# SCHEMATIC_board.net
KiCad netlist of a schematic drawn in EAGLE
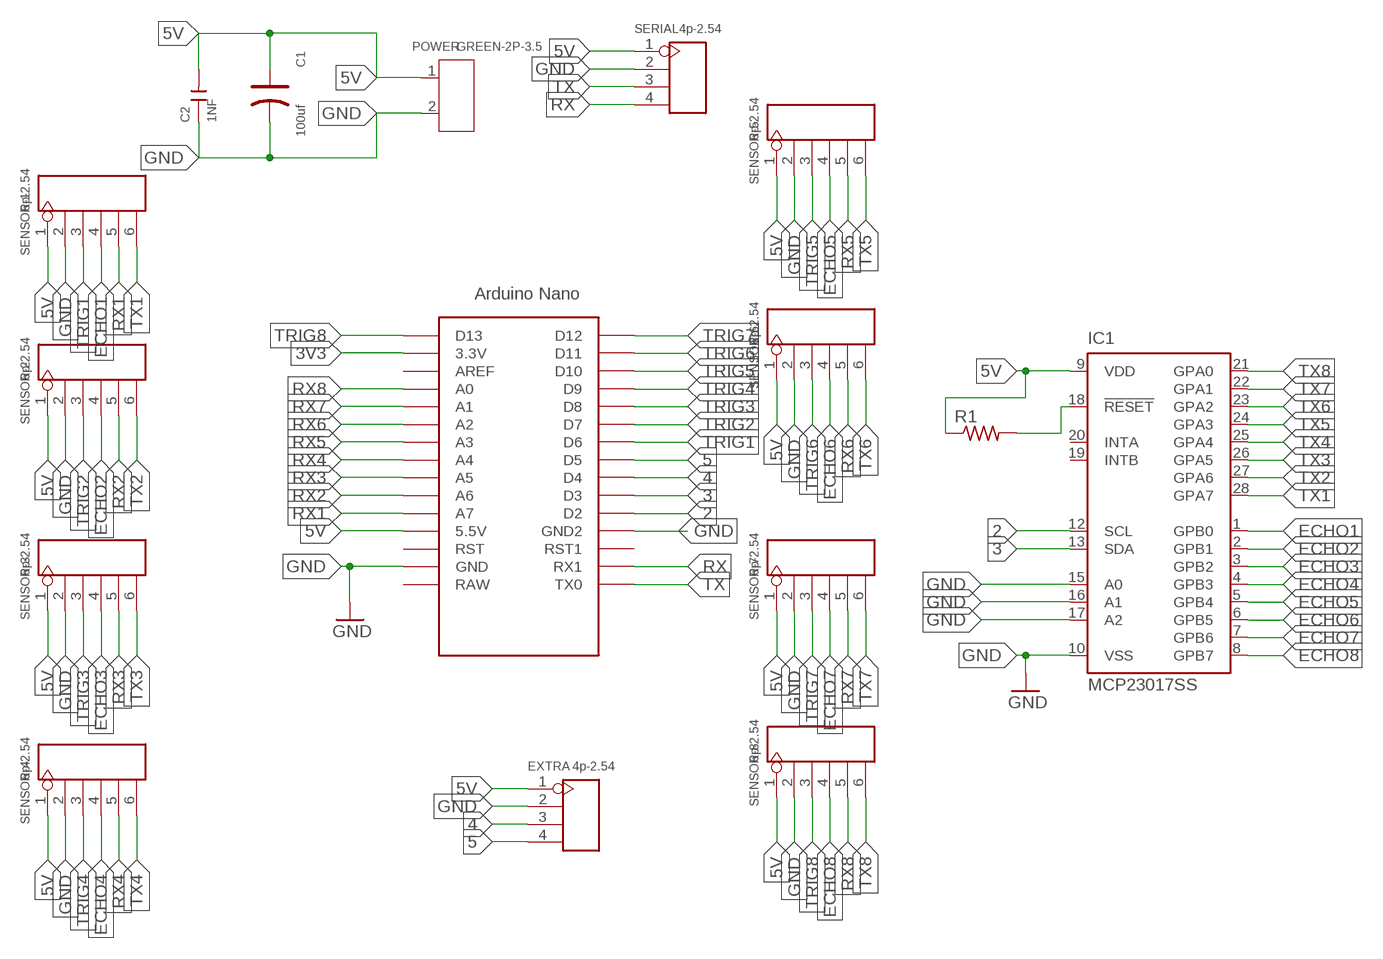
[diagram p0: schematic, sheet 1]

(export (version "E")
  (design (tool "Eeschema 10.0.6"))
  (components
    (comp (ref "C1")
      (value "100uf")
      (footprint "eagle-import:PC-D5.3MM")
      (fields (field (name "MPN") "KS 100uF/16V"))
      (libsource (lib "eagle-import") (part "DIP-ALUMINUM-100UF-16V(D5-H7MM)"))
    )
    (comp (ref "C2")
      (value "1NF")
      (footprint "eagle-import:C1206")
      (fields (field (name "MPN") "CC1206KKX7RCBB102"))
      (libsource (lib "eagle-import") (part "CERAMIC-1NF-1KV-10%-X7R?(1206)"))
    )
    (comp (ref "EXTRA")
      (value "4p-2.54")
      (footprint "eagle-import:H4-2.54")
      (fields (field (name "MPN") "P125-1104A0BS116A1"))
      (libsource (lib "eagle-import") (part "DIP-BLACK-MALE-HEADER-VERT(4P-2.54)"))
    )
    (comp (ref "IC1")
      (value "MCP23017SS")
      (footprint "eagle-import:SSOP28")
      (libsource (lib "eagle-import") (part "MCP23017SS"))
    )
    (comp (ref "POWER")
      (value "GREEN-2P-3.5")
      (footprint "eagle-import:H2-3.5-7.0X7.0MM")
      (libsource (lib "eagle-import") (part "SCREW-TERMINAL-GREEN(2P-3.5)"))
    )
    (comp (ref "R1")
      (value "R-US_M1206")
      (footprint "eagle-import:M1206")
      (libsource (lib "eagle-import") (part "R-US_M1206"))
    )
    (comp (ref "SENSOR-1")
      (value "6p-2.54")
      (footprint "eagle-import:H6-2.54")
      (fields (field (name "MPN") "F185-1106A1BSYC1"))
      (libsource (lib "eagle-import") (part "DIP-BLACK-FEMALE-HEADER-VERT(6P-2.54)"))
    )
    (comp (ref "SENSOR-2")
      (value "6p-2.54")
      (footprint "eagle-import:H6-2.54")
      (fields (field (name "MPN") "F185-1106A1BSYC1"))
      (libsource (lib "eagle-import") (part "DIP-BLACK-FEMALE-HEADER-VERT(6P-2.54)"))
    )
    (comp (ref "SENSOR-3")
      (value "6p-2.54")
      (footprint "eagle-import:H6-2.54")
      (fields (field (name "MPN") "F185-1106A1BSYC1"))
      (libsource (lib "eagle-import") (part "DIP-BLACK-FEMALE-HEADER-VERT(6P-2.54)"))
    )
    (comp (ref "SENSOR-4")
      (value "6p-2.54")
      (footprint "eagle-import:H6-2.54")
      (fields (field (name "MPN") "F185-1106A1BSYC1"))
      (libsource (lib "eagle-import") (part "DIP-BLACK-FEMALE-HEADER-VERT(6P-2.54)"))
    )
    (comp (ref "SENSOR-5")
      (value "6p-2.54")
      (footprint "eagle-import:H6-2.54")
      (fields (field (name "MPN") "F185-1106A1BSYC1"))
      (libsource (lib "eagle-import") (part "DIP-BLACK-FEMALE-HEADER-VERT(6P-2.54)"))
    )
    (comp (ref "SENSOR-6")
      (value "6p-2.54")
      (footprint "eagle-import:H6-2.54")
      (fields (field (name "MPN") "F185-1106A1BSYC1"))
      (libsource (lib "eagle-import") (part "DIP-BLACK-FEMALE-HEADER-VERT(6P-2.54)"))
    )
    (comp (ref "SENSOR-7")
      (value "6p-2.54")
      (footprint "eagle-import:H6-2.54")
      (fields (field (name "MPN") "F185-1106A1BSYC1"))
      (libsource (lib "eagle-import") (part "DIP-BLACK-FEMALE-HEADER-VERT(6P-2.54)"))
    )
    (comp (ref "SENSOR-8")
      (value "6p-2.54")
      (footprint "eagle-import:H6-2.54")
      (fields (field (name "MPN") "F185-1106A1BSYC1"))
      (libsource (lib "eagle-import") (part "DIP-BLACK-FEMALE-HEADER-VERT(6P-2.54)"))
    )
    (comp (ref "SERIAL")
      (value "4p-2.54")
      (footprint "eagle-import:H4-2.54")
      (fields (field (name "MPN") "P125-1104A0BS116A1"))
      (libsource (lib "eagle-import") (part "DIP-BLACK-MALE-HEADER-VERT(4P-2.54)"))
    )
    (comp (ref "U$1")
      (value "NANO")
      (footprint "eagle-import:NANO")
      (libsource (lib "eagle-import") (part "NANO"))
    )
  )
  (nets
    (net (code "1") (name "2") (class "Default")
      (node (ref "IC1") (pin "12") (pinfunction "SCL_12") (pintype "input"))
      (node (ref "U$1") (pin "D2") (pinfunction "D2_D2") (pintype "bidirectional"))
    )
    (net (code "2") (name "3") (class "Default")
      (node (ref "IC1") (pin "13") (pinfunction "SDA_13") (pintype "bidirectional"))
      (node (ref "U$1") (pin "D3") (pinfunction "D3_D3") (pintype "bidirectional"))
    )
    (net (code "3") (name "3V3") (class "Default")
      (node (ref "U$1") (pin "3.3V") (pinfunction "3.3V_3.3V") (pintype "bidirectional"))
    )
    (net (code "4") (name "4") (class "Default")
      (node (ref "EXTRA") (pin "3") (pinfunction "P$3_3") (pintype "bidirectional"))
      (node (ref "U$1") (pin "D4") (pinfunction "D4_D4") (pintype "bidirectional"))
    )
    (net (code "5") (name "5") (class "Default")
      (node (ref "EXTRA") (pin "4") (pinfunction "P$4_4") (pintype "bidirectional"))
      (node (ref "U$1") (pin "D5") (pinfunction "D5_D5") (pintype "bidirectional"))
    )
    (net (code "6") (name "5V") (class "Default")
      (node (ref "C1") (pin "+") (pinfunction "+_+") (pintype "passive"))
      (node (ref "C2") (pin "2") (pinfunction "2_2") (pintype "passive"))
      (node (ref "EXTRA") (pin "1") (pinfunction "P$1_1") (pintype "bidirectional"))
      (node (ref "IC1") (pin "9") (pinfunction "VDD_9") (pintype "power_in"))
      (node (ref "POWER") (pin "1") (pinfunction "1_1") (pintype "bidirectional"))
      (node (ref "R1") (pin "1") (pinfunction "1_1") (pintype "passive"))
      (node (ref "SENSOR-1") (pin "1") (pinfunction "1_1") (pintype "bidirectional"))
      (node (ref "SENSOR-2") (pin "1") (pinfunction "1_1") (pintype "bidirectional"))
      (node (ref "SENSOR-3") (pin "1") (pinfunction "1_1") (pintype "bidirectional"))
      (node (ref "SENSOR-4") (pin "1") (pinfunction "1_1") (pintype "bidirectional"))
      (node (ref "SENSOR-5") (pin "1") (pinfunction "1_1") (pintype "bidirectional"))
      (node (ref "SENSOR-6") (pin "1") (pinfunction "1_1") (pintype "bidirectional"))
      (node (ref "SENSOR-7") (pin "1") (pinfunction "1_1") (pintype "bidirectional"))
      (node (ref "SENSOR-8") (pin "1") (pinfunction "1_1") (pintype "bidirectional"))
      (node (ref "SERIAL") (pin "1") (pinfunction "P$1_1") (pintype "bidirectional"))
      (node (ref "U$1") (pin "5V") (pinfunction "5.5V_5V") (pintype "bidirectional"))
    )
    (net (code "7") (name "ECHO1") (class "Default")
      (node (ref "IC1") (pin "1") (pinfunction "GPB0_1") (pintype "bidirectional"))
      (node (ref "SENSOR-1") (pin "4") (pinfunction "4_4") (pintype "bidirectional"))
    )
    (net (code "8") (name "ECHO2") (class "Default")
      (node (ref "IC1") (pin "2") (pinfunction "GPB1_2") (pintype "bidirectional"))
      (node (ref "SENSOR-2") (pin "4") (pinfunction "4_4") (pintype "bidirectional"))
    )
    (net (code "9") (name "ECHO3") (class "Default")
      (node (ref "IC1") (pin "3") (pinfunction "GPB2_3") (pintype "bidirectional"))
      (node (ref "SENSOR-3") (pin "4") (pinfunction "4_4") (pintype "bidirectional"))
    )
    (net (code "10") (name "ECHO4") (class "Default")
      (node (ref "IC1") (pin "4") (pinfunction "GPB3_4") (pintype "bidirectional"))
      (node (ref "SENSOR-4") (pin "4") (pinfunction "4_4") (pintype "bidirectional"))
    )
    (net (code "11") (name "ECHO5") (class "Default")
      (node (ref "IC1") (pin "5") (pinfunction "GPB4_5") (pintype "bidirectional"))
      (node (ref "SENSOR-5") (pin "4") (pinfunction "4_4") (pintype "bidirectional"))
    )
    (net (code "12") (name "ECHO6") (class "Default")
      (node (ref "IC1") (pin "6") (pinfunction "GPB5_6") (pintype "bidirectional"))
      (node (ref "SENSOR-6") (pin "4") (pinfunction "4_4") (pintype "bidirectional"))
    )
    (net (code "13") (name "ECHO7") (class "Default")
      (node (ref "IC1") (pin "7") (pinfunction "GPB6_7") (pintype "bidirectional"))
      (node (ref "SENSOR-7") (pin "4") (pinfunction "4_4") (pintype "bidirectional"))
    )
    (net (code "14") (name "ECHO8") (class "Default")
      (node (ref "IC1") (pin "8") (pinfunction "GPB7_8") (pintype "bidirectional"))
      (node (ref "SENSOR-8") (pin "4") (pinfunction "4_4") (pintype "bidirectional"))
    )
    (net (code "15") (name "GND") (class "Default")
      (node (ref "C1") (pin "-") (pinfunction "-_-") (pintype "passive"))
      (node (ref "C2") (pin "1") (pinfunction "1_1") (pintype "passive"))
      (node (ref "EXTRA") (pin "2") (pinfunction "P$2_2") (pintype "bidirectional"))
      (node (ref "IC1") (pin "10") (pinfunction "VSS_10") (pintype "power_in"))
      (node (ref "IC1") (pin "15") (pinfunction "A0_15") (pintype "input"))
      (node (ref "IC1") (pin "16") (pinfunction "A1_16") (pintype "input"))
      (node (ref "IC1") (pin "17") (pinfunction "A2_17") (pintype "input"))
      (node (ref "POWER") (pin "2") (pinfunction "2_2") (pintype "bidirectional"))
      (node (ref "SENSOR-1") (pin "2") (pinfunction "2_2") (pintype "bidirectional"))
      (node (ref "SENSOR-2") (pin "2") (pinfunction "2_2") (pintype "bidirectional"))
      (node (ref "SENSOR-3") (pin "2") (pinfunction "2_2") (pintype "bidirectional"))
      (node (ref "SENSOR-4") (pin "2") (pinfunction "2_2") (pintype "bidirectional"))
      (node (ref "SENSOR-5") (pin "2") (pinfunction "2_2") (pintype "bidirectional"))
      (node (ref "SENSOR-6") (pin "2") (pinfunction "2_2") (pintype "bidirectional"))
      (node (ref "SENSOR-7") (pin "2") (pinfunction "2_2") (pintype "bidirectional"))
      (node (ref "SENSOR-8") (pin "2") (pinfunction "2_2") (pintype "bidirectional"))
      (node (ref "SERIAL") (pin "2") (pinfunction "P$2_2") (pintype "bidirectional"))
      (node (ref "U$1") (pin "GND") (pinfunction "GND_GND") (pintype "bidirectional"))
      (node (ref "U$1") (pin "GND1") (pinfunction "GND2_GND1") (pintype "bidirectional"))
    )
    (net (code "16") (name "Net-(IC1-~{RESET})") (class "Default")
      (node (ref "IC1") (pin "18") (pinfunction "~{RESET}_18") (pintype "input"))
      (node (ref "R1") (pin "2") (pinfunction "2_2") (pintype "passive"))
    )
    (net (code "17") (name "RX") (class "Default")
      (node (ref "SERIAL") (pin "4") (pinfunction "P$4_4") (pintype "bidirectional"))
      (node (ref "U$1") (pin "RX1") (pinfunction "RX1_RX1") (pintype "bidirectional"))
    )
    (net (code "18") (name "RX1") (class "Default")
      (node (ref "SENSOR-1") (pin "5") (pinfunction "5_5") (pintype "bidirectional"))
      (node (ref "U$1") (pin "A7") (pinfunction "A7_A7") (pintype "bidirectional"))
    )
    (net (code "19") (name "RX2") (class "Default")
      (node (ref "SENSOR-2") (pin "5") (pinfunction "5_5") (pintype "bidirectional"))
      (node (ref "U$1") (pin "A6") (pinfunction "A6_A6") (pintype "bidirectional"))
    )
    (net (code "20") (name "RX3") (class "Default")
      (node (ref "SENSOR-3") (pin "5") (pinfunction "5_5") (pintype "bidirectional"))
      (node (ref "U$1") (pin "A5") (pinfunction "A5_A5") (pintype "bidirectional"))
    )
    (net (code "21") (name "RX4") (class "Default")
      (node (ref "SENSOR-4") (pin "5") (pinfunction "5_5") (pintype "bidirectional"))
      (node (ref "U$1") (pin "A4") (pinfunction "A4_A4") (pintype "bidirectional"))
    )
    (net (code "22") (name "RX5") (class "Default")
      (node (ref "SENSOR-5") (pin "5") (pinfunction "5_5") (pintype "bidirectional"))
      (node (ref "U$1") (pin "A3") (pinfunction "A3_A3") (pintype "bidirectional"))
    )
    (net (code "23") (name "RX6") (class "Default")
      (node (ref "SENSOR-6") (pin "5") (pinfunction "5_5") (pintype "bidirectional"))
      (node (ref "U$1") (pin "A2") (pinfunction "A2_A2") (pintype "bidirectional"))
    )
    (net (code "24") (name "RX7") (class "Default")
      (node (ref "SENSOR-7") (pin "5") (pinfunction "5_5") (pintype "bidirectional"))
      (node (ref "U$1") (pin "A1") (pinfunction "A1_A1") (pintype "bidirectional"))
    )
    (net (code "25") (name "RX8") (class "Default")
      (node (ref "SENSOR-8") (pin "5") (pinfunction "5_5") (pintype "bidirectional"))
      (node (ref "U$1") (pin "A0") (pinfunction "A0_A0") (pintype "bidirectional"))
    )
    (net (code "26") (name "TRIG1") (class "Default")
      (node (ref "SENSOR-1") (pin "3") (pinfunction "3_3") (pintype "bidirectional"))
      (node (ref "U$1") (pin "D6") (pinfunction "D6_D6") (pintype "bidirectional"))
    )
    (net (code "27") (name "TRIG2") (class "Default")
      (node (ref "SENSOR-2") (pin "3") (pinfunction "3_3") (pintype "bidirectional"))
      (node (ref "U$1") (pin "D7") (pinfunction "D7_D7") (pintype "bidirectional"))
    )
    (net (code "28") (name "TRIG3") (class "Default")
      (node (ref "SENSOR-3") (pin "3") (pinfunction "3_3") (pintype "bidirectional"))
      (node (ref "U$1") (pin "D8") (pinfunction "D8_D8") (pintype "bidirectional"))
    )
    (net (code "29") (name "TRIG4") (class "Default")
      (node (ref "SENSOR-4") (pin "3") (pinfunction "3_3") (pintype "bidirectional"))
      (node (ref "U$1") (pin "D9") (pinfunction "D9_D9") (pintype "bidirectional"))
    )
    (net (code "30") (name "TRIG5") (class "Default")
      (node (ref "SENSOR-5") (pin "3") (pinfunction "3_3") (pintype "bidirectional"))
      (node (ref "U$1") (pin "D10") (pinfunction "D10_D10") (pintype "bidirectional"))
    )
    (net (code "31") (name "TRIG6") (class "Default")
      (node (ref "SENSOR-6") (pin "3") (pinfunction "3_3") (pintype "bidirectional"))
      (node (ref "U$1") (pin "D11") (pinfunction "D11_D11") (pintype "bidirectional"))
    )
    (net (code "32") (name "TRIG7") (class "Default")
      (node (ref "SENSOR-7") (pin "3") (pinfunction "3_3") (pintype "bidirectional"))
      (node (ref "U$1") (pin "D12") (pinfunction "D12_D12") (pintype "bidirectional"))
    )
    (net (code "33") (name "TRIG8") (class "Default")
      (node (ref "SENSOR-8") (pin "3") (pinfunction "3_3") (pintype "bidirectional"))
      (node (ref "U$1") (pin "D13") (pinfunction "D13_D13") (pintype "bidirectional"))
    )
    (net (code "34") (name "TX") (class "Default")
      (node (ref "SERIAL") (pin "3") (pinfunction "P$3_3") (pintype "bidirectional"))
      (node (ref "U$1") (pin "TX0") (pinfunction "TX0_TX0") (pintype "bidirectional"))
    )
    (net (code "35") (name "TX1") (class "Default")
      (node (ref "IC1") (pin "28") (pinfunction "GPA7_28") (pintype "bidirectional"))
      (node (ref "SENSOR-1") (pin "6") (pinfunction "6_6") (pintype "bidirectional"))
    )
    (net (code "36") (name "TX2") (class "Default")
      (node (ref "IC1") (pin "27") (pinfunction "GPA6_27") (pintype "bidirectional"))
      (node (ref "SENSOR-2") (pin "6") (pinfunction "6_6") (pintype "bidirectional"))
    )
    (net (code "37") (name "TX3") (class "Default")
      (node (ref "IC1") (pin "26") (pinfunction "GPA5_26") (pintype "bidirectional"))
      (node (ref "SENSOR-3") (pin "6") (pinfunction "6_6") (pintype "bidirectional"))
    )
    (net (code "38") (name "TX4") (class "Default")
      (node (ref "IC1") (pin "25") (pinfunction "GPA4_25") (pintype "bidirectional"))
      (node (ref "SENSOR-4") (pin "6") (pinfunction "6_6") (pintype "bidirectional"))
    )
    (net (code "39") (name "TX5") (class "Default")
      (node (ref "IC1") (pin "24") (pinfunction "GPA3_24") (pintype "bidirectional"))
      (node (ref "SENSOR-5") (pin "6") (pinfunction "6_6") (pintype "bidirectional"))
    )
    (net (code "40") (name "TX6") (class "Default")
      (node (ref "IC1") (pin "23") (pinfunction "GPA2_23") (pintype "bidirectional"))
      (node (ref "SENSOR-6") (pin "6") (pinfunction "6_6") (pintype "bidirectional"))
    )
    (net (code "41") (name "TX7") (class "Default")
      (node (ref "IC1") (pin "22") (pinfunction "GPA1_22") (pintype "bidirectional"))
      (node (ref "SENSOR-7") (pin "6") (pinfunction "6_6") (pintype "bidirectional"))
    )
    (net (code "42") (name "TX8") (class "Default")
      (node (ref "IC1") (pin "21") (pinfunction "GPA0_21") (pintype "bidirectional"))
      (node (ref "SENSOR-8") (pin "6") (pinfunction "6_6") (pintype "bidirectional"))
    )
    (net (code "43") (name "unconnected-(IC1-INTA-Pad20)") (class "Default")
      (node (ref "IC1") (pin "20") (pinfunction "INTA_20") (pintype "output"))
    )
    (net (code "44") (name "unconnected-(IC1-INTB-Pad19)") (class "Default")
      (node (ref "IC1") (pin "19") (pinfunction "INTB_19") (pintype "output"))
    )
    (net (code "45") (name "unconnected-(U$1-PadAREF)") (class "Default")
      (node (ref "U$1") (pin "AREF") (pinfunction "AREF_AREF") (pintype "bidirectional"))
    )
    (net (code "46") (name "unconnected-(U$1-PadICSP1)") (class "Default")
      (node (ref "U$1") (pin "ICSP1") (pinfunction "ICSP1_ICSP1") (pintype "bidirectional"))
    )
    (net (code "47") (name "unconnected-(U$1-PadICSP2)") (class "Default")
      (node (ref "U$1") (pin "ICSP2") (pinfunction "ICSP2_ICSP2") (pintype "bidirectional"))
    )
    (net (code "48") (name "unconnected-(U$1-PadICSP3)") (class "Default")
      (node (ref "U$1") (pin "ICSP3") (pinfunction "ICSP3_ICSP3") (pintype "bidirectional"))
    )
    (net (code "49") (name "unconnected-(U$1-PadICSP4)") (class "Default")
      (node (ref "U$1") (pin "ICSP4") (pinfunction "ICSP4_ICSP4") (pintype "bidirectional"))
    )
    (net (code "50") (name "unconnected-(U$1-PadICSP5)") (class "Default")
      (node (ref "U$1") (pin "ICSP5") (pinfunction "ICSP5_ICSP5") (pintype "bidirectional"))
    )
    (net (code "51") (name "unconnected-(U$1-PadICSP6)") (class "Default")
      (node (ref "U$1") (pin "ICSP6") (pinfunction "ICSP6_ICSP6") (pintype "bidirectional"))
    )
    (net (code "52") (name "unconnected-(U$1-PadRAW)") (class "Default")
      (node (ref "U$1") (pin "RAW") (pinfunction "RAW_RAW") (pintype "bidirectional"))
    )
    (net (code "53") (name "unconnected-(U$1-PadRST)") (class "Default")
      (node (ref "U$1") (pin "RST") (pinfunction "RST_RST") (pintype "bidirectional"))
    )
    (net (code "54") (name "unconnected-(U$1-PadRST1)") (class "Default")
      (node (ref "U$1") (pin "RST1") (pinfunction "RST1_RST1") (pintype "bidirectional"))
    )
  )
)
